# LCD.net
KiCad netlist of a schematic drawn in Altium Designer
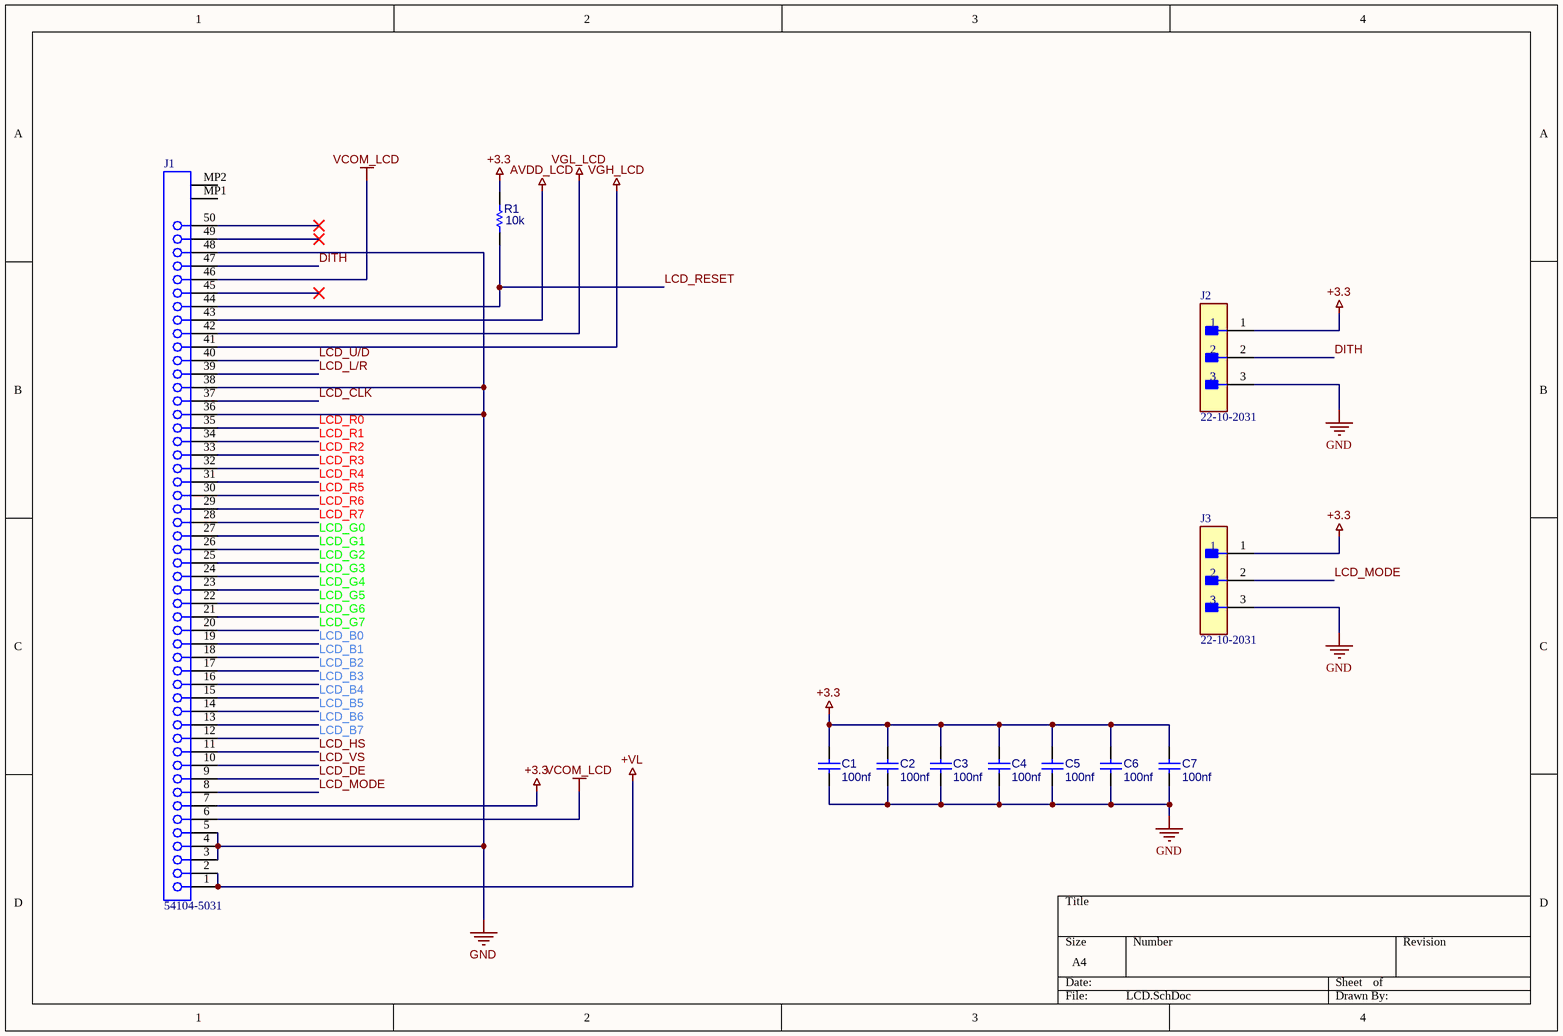
[diagram p0: LCD.SchDoc]

(export (version "E")
  (design (tool "Eeschema 10.0.6"))
  (components
    (comp (ref "C1")
      (value "100nf")
      (footprint "CAPC2013X70X45NL10T25")
      (fields (field (name "PART NUMBER") "GRM216R61E105KA12D") (field (name "MANUFACTURER") "Murata"))
      (libsource (lib "Altium Content Vault") (part "CAP"))
    )
    (comp (ref "C2")
      (value "100nf")
      (footprint "CAPC2013X70X45NL10T25")
      (fields (field (name "PART NUMBER") "GRM216R61E105KA12D") (field (name "MANUFACTURER") "Murata"))
      (libsource (lib "Altium Content Vault") (part "CAP"))
    )
    (comp (ref "C3")
      (value "100nf")
      (footprint "CAPC2013X70X45NL10T25")
      (fields (field (name "PART NUMBER") "GRM216R61E105KA12D") (field (name "MANUFACTURER") "Murata"))
      (libsource (lib "Altium Content Vault") (part "CAP"))
    )
    (comp (ref "C4")
      (value "100nf")
      (footprint "CAPC2013X70X45NL10T25")
      (fields (field (name "PART NUMBER") "GRM216R61E105KA12D") (field (name "MANUFACTURER") "Murata"))
      (libsource (lib "Altium Content Vault") (part "CAP"))
    )
    (comp (ref "C5")
      (value "100nf")
      (footprint "CAPC2013X70X45NL10T25")
      (fields (field (name "PART NUMBER") "GRM216R61E105KA12D") (field (name "MANUFACTURER") "Murata"))
      (libsource (lib "Altium Content Vault") (part "CAP"))
    )
    (comp (ref "C6")
      (value "100nf")
      (footprint "CAPC2013X70X45NL10T25")
      (fields (field (name "PART NUMBER") "GRM216R61E105KA12D") (field (name "MANUFACTURER") "Murata"))
      (libsource (lib "Altium Content Vault") (part "CAP"))
    )
    (comp (ref "C7")
      (value "100nf")
      (footprint "CAPC2013X70X45NL10T25")
      (fields (field (name "PART NUMBER") "GRM216R61E105KA12D") (field (name "MANUFACTURER") "Murata"))
      (libsource (lib "Altium Content Vault") (part "CAP"))
    )
    (comp (ref "J1")
      (value "54104-5031")
      (footprint "MOLX-54104-5031")
      (fields (field (name "MANUFACTURER") "Molex"))
      (libsource (lib "Altium Content Vault") (part "MOLX-54104-5031"))
    )
    (comp (ref "J2")
      (value "22-10-2031")
      (footprint "FP-22-10-2031-MFG")
      (description "CONN HEADER VERT 3POS 2.54MM")
      (libsource (lib "Altium Content Vault") (part "0d3f023dd272f625e17a2be33dea85f"))
    )
    (comp (ref "J3")
      (value "22-10-2031")
      (footprint "FP-22-10-2031-MFG")
      (description "CONN HEADER VERT 3POS 2.54MM")
      (libsource (lib "Altium Content Vault") (part "0d3f023dd272f625e17a2be33dea85f"))
    )
    (comp (ref "R1")
      (value "10k")
      (footprint "RESC2013X60X35ML10T20")
      (description "Chip Resistor, 1 KOhm, +/- 1%, 125 mW, -55 to 155 degC, 0805 (2012 Metric), RoHS, Tape and Reel")
      (fields (field (name "TOLERANCE") "1%") (field (name "MANUFACTURER") "Yageo"))
      (libsource (lib "Altium Content Vault") (part "RES-2"))
    )
  )
  (nets
    (net (code "1") (name "+3.3") (class "Default")
      (node (ref "C1") (pin "2") (pinfunction "2_2") (pintype "passive"))
      (node (ref "C2") (pin "2") (pinfunction "2_2") (pintype "passive"))
      (node (ref "C3") (pin "2") (pinfunction "2_2") (pintype "passive"))
      (node (ref "C4") (pin "2") (pinfunction "2_2") (pintype "passive"))
      (node (ref "C5") (pin "2") (pinfunction "2_2") (pintype "passive"))
      (node (ref "C6") (pin "2") (pinfunction "2_2") (pintype "passive"))
      (node (ref "C7") (pin "2") (pinfunction "2_2") (pintype "passive"))
      (node (ref "J1") (pin "7") (pinfunction "7_7") (pintype "passive"))
      (node (ref "J2") (pin "1") (pinfunction "1_1") (pintype "passive"))
      (node (ref "J3") (pin "1") (pinfunction "1_1") (pintype "passive"))
      (node (ref "R1") (pin "1") (pinfunction "1_1") (pintype "passive"))
    )
    (net (code "2") (name "+VL") (class "Default")
      (node (ref "J1") (pin "1") (pinfunction "1_1") (pintype "passive"))
      (node (ref "J1") (pin "2") (pinfunction "2_2") (pintype "passive"))
    )
    (net (code "3") (name "/DITH") (class "Default")
      (node (ref "J1") (pin "47") (pinfunction "47_47") (pintype "passive"))
      (node (ref "J2") (pin "2") (pinfunction "2_2") (pintype "passive"))
    )
    (net (code "4") (name "/LCD_B0") (class "Default")
      (node (ref "J1") (pin "19") (pinfunction "19_19") (pintype "passive"))
    )
    (net (code "5") (name "/LCD_B1") (class "Default")
      (node (ref "J1") (pin "18") (pinfunction "18_18") (pintype "passive"))
    )
    (net (code "6") (name "/LCD_B2") (class "Default")
      (node (ref "J1") (pin "17") (pinfunction "17_17") (pintype "passive"))
    )
    (net (code "7") (name "/LCD_B3") (class "Default")
      (node (ref "J1") (pin "16") (pinfunction "16_16") (pintype "passive"))
    )
    (net (code "8") (name "/LCD_B4") (class "Default")
      (node (ref "J1") (pin "15") (pinfunction "15_15") (pintype "passive"))
    )
    (net (code "9") (name "/LCD_B5") (class "Default")
      (node (ref "J1") (pin "14") (pinfunction "14_14") (pintype "passive"))
    )
    (net (code "10") (name "/LCD_B6") (class "Default")
      (node (ref "J1") (pin "13") (pinfunction "13_13") (pintype "passive"))
    )
    (net (code "11") (name "/LCD_B7") (class "Default")
      (node (ref "J1") (pin "12") (pinfunction "12_12") (pintype "passive"))
    )
    (net (code "12") (name "/LCD_CLK") (class "Default")
      (node (ref "J1") (pin "37") (pinfunction "37_37") (pintype "passive"))
    )
    (net (code "13") (name "/LCD_DE") (class "Default")
      (node (ref "J1") (pin "9") (pinfunction "9_9") (pintype "passive"))
    )
    (net (code "14") (name "/LCD_G0") (class "Default")
      (node (ref "J1") (pin "27") (pinfunction "27_27") (pintype "passive"))
    )
    (net (code "15") (name "/LCD_G1") (class "Default")
      (node (ref "J1") (pin "26") (pinfunction "26_26") (pintype "passive"))
    )
    (net (code "16") (name "/LCD_G2") (class "Default")
      (node (ref "J1") (pin "25") (pinfunction "25_25") (pintype "passive"))
    )
    (net (code "17") (name "/LCD_G3") (class "Default")
      (node (ref "J1") (pin "24") (pinfunction "24_24") (pintype "passive"))
    )
    (net (code "18") (name "/LCD_G4") (class "Default")
      (node (ref "J1") (pin "23") (pinfunction "23_23") (pintype "passive"))
    )
    (net (code "19") (name "/LCD_G5") (class "Default")
      (node (ref "J1") (pin "22") (pinfunction "22_22") (pintype "passive"))
    )
    (net (code "20") (name "/LCD_G6") (class "Default")
      (node (ref "J1") (pin "21") (pinfunction "21_21") (pintype "passive"))
    )
    (net (code "21") (name "/LCD_G7") (class "Default")
      (node (ref "J1") (pin "20") (pinfunction "20_20") (pintype "passive"))
    )
    (net (code "22") (name "/LCD_HS") (class "Default")
      (node (ref "J1") (pin "11") (pinfunction "11_11") (pintype "passive"))
    )
    (net (code "23") (name "/LCD_L{slash}R") (class "Default")
      (node (ref "J1") (pin "39") (pinfunction "39_39") (pintype "passive"))
    )
    (net (code "24") (name "/LCD_MODE") (class "Default")
      (node (ref "J1") (pin "8") (pinfunction "8_8") (pintype "passive"))
      (node (ref "J3") (pin "2") (pinfunction "2_2") (pintype "passive"))
    )
    (net (code "25") (name "/LCD_R0") (class "Default")
      (node (ref "J1") (pin "35") (pinfunction "35_35") (pintype "passive"))
    )
    (net (code "26") (name "/LCD_R1") (class "Default")
      (node (ref "J1") (pin "34") (pinfunction "34_34") (pintype "passive"))
    )
    (net (code "27") (name "/LCD_R2") (class "Default")
      (node (ref "J1") (pin "33") (pinfunction "33_33") (pintype "passive"))
    )
    (net (code "28") (name "/LCD_R3") (class "Default")
      (node (ref "J1") (pin "32") (pinfunction "32_32") (pintype "passive"))
    )
    (net (code "29") (name "/LCD_R4") (class "Default")
      (node (ref "J1") (pin "31") (pinfunction "31_31") (pintype "passive"))
    )
    (net (code "30") (name "/LCD_R5") (class "Default")
      (node (ref "J1") (pin "30") (pinfunction "30_30") (pintype "passive"))
    )
    (net (code "31") (name "/LCD_R6") (class "Default")
      (node (ref "J1") (pin "29") (pinfunction "29_29") (pintype "passive"))
    )
    (net (code "32") (name "/LCD_R7") (class "Default")
      (node (ref "J1") (pin "28") (pinfunction "28_28") (pintype "passive"))
    )
    (net (code "33") (name "/LCD_RESET") (class "Default")
      (node (ref "J1") (pin "44") (pinfunction "44_44") (pintype "passive"))
      (node (ref "R1") (pin "2") (pinfunction "2_2") (pintype "passive"))
    )
    (net (code "34") (name "/LCD_U{slash}D") (class "Default")
      (node (ref "J1") (pin "40") (pinfunction "40_40") (pintype "passive"))
    )
    (net (code "35") (name "/LCD_VS") (class "Default")
      (node (ref "J1") (pin "10") (pinfunction "10_10") (pintype "passive"))
    )
    (net (code "36") (name "AVDD_LCD") (class "Default")
      (node (ref "J1") (pin "43") (pinfunction "43_43") (pintype "passive"))
    )
    (net (code "37") (name "GND") (class "Default")
      (node (ref "C1") (pin "1") (pinfunction "1_1") (pintype "passive"))
      (node (ref "C2") (pin "1") (pinfunction "1_1") (pintype "passive"))
      (node (ref "C3") (pin "1") (pinfunction "1_1") (pintype "passive"))
      (node (ref "C4") (pin "1") (pinfunction "1_1") (pintype "passive"))
      (node (ref "C5") (pin "1") (pinfunction "1_1") (pintype "passive"))
      (node (ref "C6") (pin "1") (pinfunction "1_1") (pintype "passive"))
      (node (ref "C7") (pin "1") (pinfunction "1_1") (pintype "passive"))
      (node (ref "J1") (pin "3") (pinfunction "3_3") (pintype "passive"))
      (node (ref "J1") (pin "36") (pinfunction "36_36") (pintype "passive"))
      (node (ref "J1") (pin "38") (pinfunction "38_38") (pintype "passive"))
      (node (ref "J1") (pin "4") (pinfunction "4_4") (pintype "passive"))
      (node (ref "J1") (pin "48") (pinfunction "48_48") (pintype "passive"))
      (node (ref "J1") (pin "5") (pinfunction "5_5") (pintype "passive"))
      (node (ref "J2") (pin "3") (pinfunction "3_3") (pintype "passive"))
      (node (ref "J3") (pin "3") (pinfunction "3_3") (pintype "passive"))
    )
    (net (code "38") (name "VCOM_LCD") (class "Default")
      (node (ref "J1") (pin "46") (pinfunction "46_46") (pintype "passive"))
      (node (ref "J1") (pin "6") (pinfunction "6_6") (pintype "passive"))
    )
    (net (code "39") (name "VGH_LCD") (class "Default")
      (node (ref "J1") (pin "41") (pinfunction "41_41") (pintype "passive"))
    )
    (net (code "40") (name "VGL_LCD") (class "Default")
      (node (ref "J1") (pin "42") (pinfunction "42_42") (pintype "passive"))
    )
    (net (code "41") (name "unconnected-(J1-Pad45)") (class "Default")
      (node (ref "J1") (pin "45") (pinfunction "45_45") (pintype "passive+no_connect"))
    )
    (net (code "42") (name "unconnected-(J1-Pad49)") (class "Default")
      (node (ref "J1") (pin "49") (pinfunction "49_49") (pintype "passive+no_connect"))
    )
    (net (code "43") (name "unconnected-(J1-Pad50)") (class "Default")
      (node (ref "J1") (pin "50") (pinfunction "50_50") (pintype "passive+no_connect"))
    )
    (net (code "44") (name "unconnected-(J1-PadMP1)") (class "Default")
      (node (ref "J1") (pin "MP1") (pinfunction "MP1_MP1") (pintype "passive"))
    )
    (net (code "45") (name "unconnected-(J1-PadMP2)") (class "Default")
      (node (ref "J1") (pin "MP2") (pinfunction "MP2_MP2") (pintype "passive"))
    )
  )
)
